# CanToUart.net
KiCad netlist of a schematic drawn in EasyEDA Pro
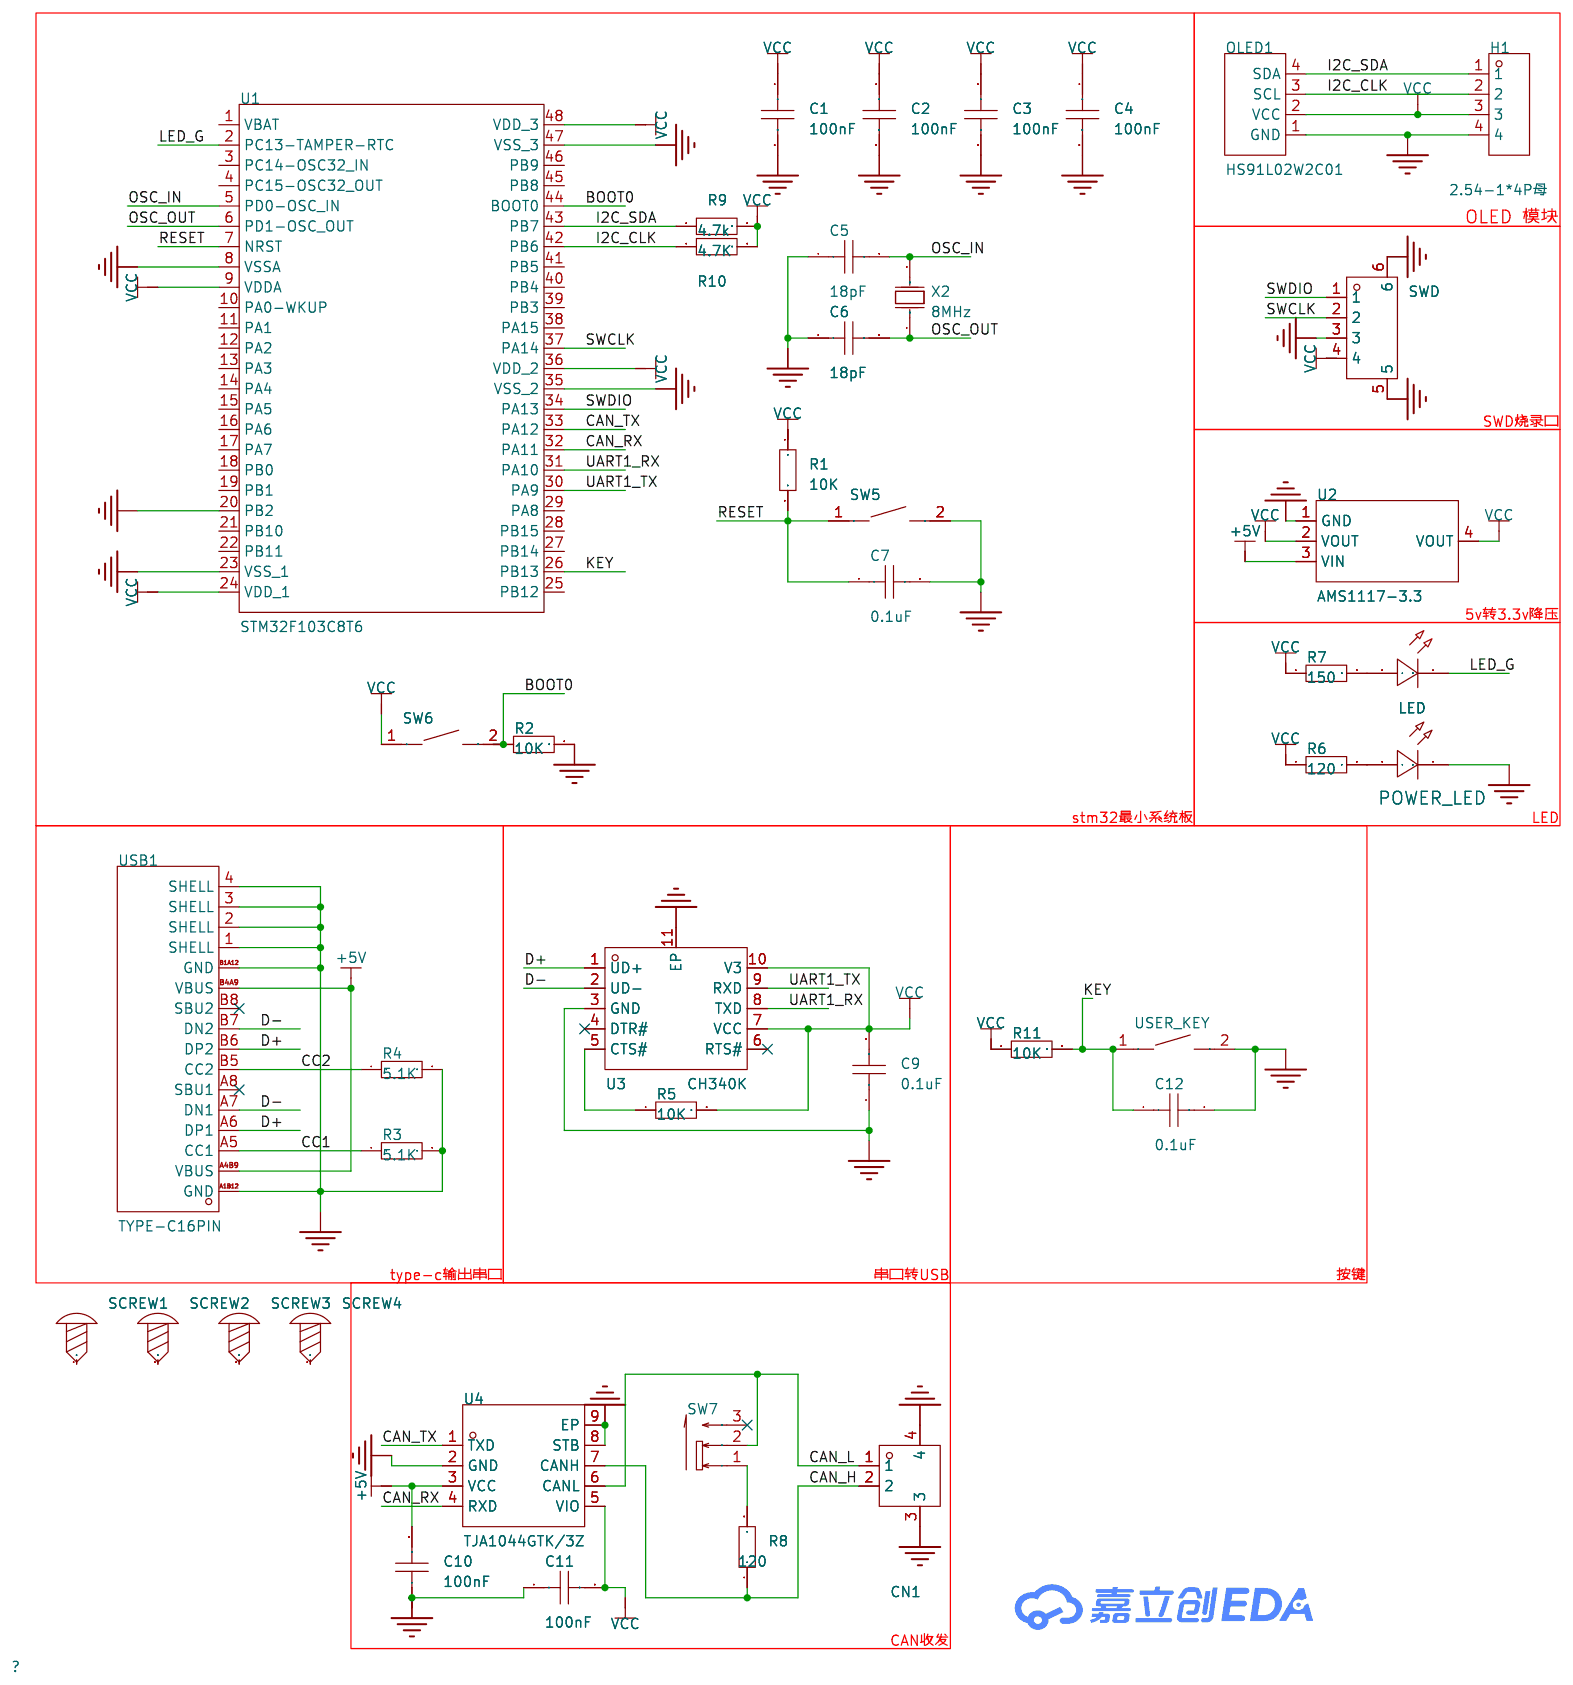
[diagram p0: schematic sheet]

(export (version "E")
  (design (tool "Eeschema 10.0.6"))
  (components
    (comp (ref "C1")
      (value "100nF")
      (footprint "easyedapro:C0603")
      (description "容值:100nF;精度:±10%;额定电压:50V;温度系数:X7R;")
      (fields
        (field (name "Manufacturer Part") "CGA0603X7R104K500JT")
        (field (name "Manufacturer") "HRE(芯声)")
      )
      (libsource (lib "easyedapro") (part "CGA0603X7R104K500JT"))
    )
    (comp (ref "C2")
      (value "100nF")
      (footprint "easyedapro:C0603")
      (description "容值:100nF;精度:±10%;额定电压:50V;温度系数:X7R;")
      (fields
        (field (name "Manufacturer Part") "CGA0603X7R104K500JT")
        (field (name "Manufacturer") "HRE(芯声)")
      )
      (libsource (lib "easyedapro") (part "CGA0603X7R104K500JT"))
    )
    (comp (ref "C3")
      (value "100nF")
      (footprint "easyedapro:C0603")
      (description "容值:100nF;精度:±10%;额定电压:50V;温度系数:X7R;")
      (fields
        (field (name "Manufacturer Part") "CGA0603X7R104K500JT")
        (field (name "Manufacturer") "HRE(芯声)")
      )
      (libsource (lib "easyedapro") (part "CGA0603X7R104K500JT"))
    )
    (comp (ref "C4")
      (value "100nF")
      (footprint "easyedapro:C0603")
      (description "容值:100nF;精度:±10%;额定电压:50V;温度系数:X7R;")
      (fields
        (field (name "Manufacturer Part") "CGA0603X7R104K500JT")
        (field (name "Manufacturer") "HRE(芯声)")
      )
      (libsource (lib "easyedapro") (part "CGA0603X7R104K500JT"))
    )
    (comp (ref "C5")
      (value "18pF")
      (footprint "easyedapro:C0603")
      (libsource (lib "easyedapro") (part "Capacitance"))
    )
    (comp (ref "C6")
      (value "18pF")
      (footprint "easyedapro:C0603")
      (libsource (lib "easyedapro") (part "Capacitance"))
    )
    (comp (ref "C7")
      (value "0.1uF")
      (footprint "easyedapro:C0603")
      (libsource (lib "easyedapro") (part "Capacitance"))
    )
    (comp (ref "C9")
      (value "0.1uF")
      (footprint "easyedapro:C0603")
      (libsource (lib "easyedapro") (part "Capacitance"))
    )
    (comp (ref "C10")
      (value "100nF")
      (footprint "easyedapro:C0603")
      (libsource (lib "easyedapro") (part "Capacitance"))
    )
    (comp (ref "C11")
      (value "100nF")
      (footprint "easyedapro:C0603")
      (libsource (lib "easyedapro") (part "Capacitance"))
    )
    (comp (ref "C12")
      (value "0.1uF")
      (footprint "easyedapro:C0603")
      (libsource (lib "easyedapro") (part "Capacitance"))
    )
    (comp (ref "CN1")
      (value "WAFER-GH1.25-2PWB")
      (footprint "easyedapro:CONN-TH_2P-P1.25_XUNPU_WAFER-GH1.25-2PWB")
      (fields (field (name "Manufacturer") "XUNPU(讯普)"))
      (libsource (lib "easyedapro") (part "WAFER-GH1.25-2PWB"))
    )
    (comp (ref "H1")
      (value "2.54-1*4P母")
      (footprint "easyedapro:HDR-TH_4P-P2.54-V-F")
      (fields (field (name "Manufacturer") "BOOMELE(博穆精密)"))
      (libsource (lib "easyedapro") (part "2.54-1*4P母"))
    )
    (comp (ref "LED")
      (value "~")
      (footprint "easyedapro:LED_0603")
      (libsource (lib "easyedapro") (part "LED_G"))
    )
    (comp (ref "OLED1")
      (value "HS91L02W2C01")
      (footprint "easyedapro:OLED-TH_L38.0-W12.0_HS91L02W2C01")
      (description "主控芯片:SSD1306;接口类型:I2C;尺寸(inch):0.91;像素分辨率:128x32;")
      (fields (field (name "Manufacturer") "HS(汉昇)"))
      (libsource (lib "easyedapro") (part "HS91L02W2C01"))
    )
    (comp (ref "POWER_LED")
      (value "~")
      (footprint "easyedapro:LED_0603")
      (libsource (lib "easyedapro") (part "LED_R"))
    )
    (comp (ref "R1") (value "10K") (footprint "easyedapro:R0603") (libsource (lib "easyedapro") (part "电阻")))
    (comp (ref "R2") (value "10K") (footprint "easyedapro:R0603") (libsource (lib "easyedapro") (part "电阻")))
    (comp (ref "R3") (value "5.1K") (footprint "easyedapro:R0603") (libsource (lib "easyedapro") (part "电阻")))
    (comp (ref "R4") (value "5.1K") (footprint "easyedapro:R0603") (libsource (lib "easyedapro") (part "电阻")))
    (comp (ref "R5") (value "10K") (footprint "easyedapro:R0603") (libsource (lib "easyedapro") (part "电阻")))
    (comp (ref "R6") (value "120") (footprint "easyedapro:R0603") (libsource (lib "easyedapro") (part "电阻")))
    (comp (ref "R7") (value "150") (footprint "easyedapro:R0603") (libsource (lib "easyedapro") (part "电阻")))
    (comp (ref "R8") (value "120") (footprint "easyedapro:R0603") (libsource (lib "easyedapro") (part "电阻")))
    (comp (ref "R9") (value "4.7k") (footprint "easyedapro:R0603") (libsource (lib "easyedapro") (part "电阻")))
    (comp (ref "R10")
      (value "4.7K")
      (footprint "easyedapro:R0603")
      (libsource (lib "easyedapro") (part "电阻"))
    )
    (comp (ref "R11") (value "10K") (footprint "easyedapro:R0603") (libsource (lib "easyedapro") (part "电阻")))
    (comp (ref "SCREW1")
      (value "~")
      (footprint "easyedapro:M2螺丝")
      (libsource (lib "easyedapro") (part "螺丝孔"))
    )
    (comp (ref "SCREW2")
      (value "~")
      (footprint "easyedapro:M2螺丝")
      (libsource (lib "easyedapro") (part "螺丝孔"))
    )
    (comp (ref "SCREW3")
      (value "~")
      (footprint "easyedapro:M2螺丝")
      (libsource (lib "easyedapro") (part "螺丝孔"))
    )
    (comp (ref "SCREW4")
      (value "~")
      (footprint "easyedapro:M2螺丝")
      (libsource (lib "easyedapro") (part "螺丝孔"))
    )
    (comp (ref "SW5")
      (value "TS-1088-AR02016")
      (footprint "easyedapro:SW-SMD_L3.9-W3.0-P4.45")
      (fields (field (name "Manufacturer") "XUNPU(讯普)"))
      (libsource (lib "easyedapro") (part "TS-1088-AR02016"))
    )
    (comp (ref "SW6")
      (value "TS-1088-AR02016")
      (footprint "easyedapro:SW-SMD_L3.9-W3.0-P4.45")
      (fields (field (name "Manufacturer") "XUNPU(讯普)"))
      (libsource (lib "easyedapro") (part "TS-1088-AR02016"))
    )
    (comp (ref "SW7")
      (value "MST-22D18G2 3J")
      (footprint "easyedapro:SW-SMD_SHOUHAN_MST-22D18G23J_C2875122")
      (description "电路结构:单刀双掷;安装方式:立贴;开关颜色:-;额定电流(DC):50mA;额定电压(DC):12V;额定电流(AC):-;额定电压(AC):-;机械寿命:1万次;")
      (fields (field (name "Manufacturer") "SHOU HAN(首韩)"))
      (libsource (lib "easyedapro") (part "MST-22D18G2 3J_C2875122"))
    )
    (comp (ref "SWD")
      (value "532610471")
      (footprint "easyedapro:CONN-SMD_4P-P1.25_53261-0471")
      (fields (field (name "Manufacturer") "MOLEX"))
      (libsource (lib "easyedapro") (part "53261-0471"))
    )
    (comp (ref "U1")
      (value "STM32F103C8T6")
      (footprint "easyedapro:LQFP-48_L7.0-W7.0-P0.50-LS9.0-BL")
      (description "CPU内核:ARM-M3;CPU最大主频:72MHz;应用领域:-;")
      (fields (field (name "Manufacturer") "ST(意法半导体)"))
      (libsource (lib "easyedapro") (part "STM32F103C8T6"))
    )
    (comp (ref "U2")
      (value "AMS1117-3.3")
      (footprint "easyedapro:SOT-223-3_L6.5-W3.4-P2.30-LS7.0-BR")
      (description "输出类型:固定;工作电压:16V;输出电压:3.3V;输出电流:1A;电源纹波抑制比(PSRR):72dB@(120Hz);输出极性:正极;")
      (fields (field (name "Manufacturer") "AMS"))
      (libsource (lib "easyedapro") (part "AMS1117-3.3"))
    )
    (comp (ref "U3")
      (value "CH340K")
      (footprint "easyedapro:ESOP-10_L4.9-W3.9-P1.00-LS6.2-BL-EP")
      (description "应用功能:USB转串口;接口协议:USB 2.0;通道数:-;数据速率:2Mbps;")
      (fields (field (name "Manufacturer") "WCH(南京沁恒)"))
      (libsource (lib "easyedapro") (part "CH340K"))
    )
    (comp (ref "U4")
      (value "TJA1044GTK/3Z")
      (footprint "easyedapro:HVSON-8_L3.0-W3.0-P0.65-BL-EP")
      (description "类型:CAN收发器;数据速率:5Mbps;")
      (fields (field (name "Manufacturer") "NXP(恩智浦)"))
      (libsource (lib "easyedapro") (part "TJA1044GTK/3Z"))
    )
    (comp (ref "USB1")
      (value "TYPE-C16PIN")
      (footprint "easyedapro:USB-C-SMD_TYPE-C16PIN")
      (description "连接器类型:Type-C;协议标准:USB 3.1;公母:母;安装方式:卧贴;触点数量:16P;端口数量:1;额定电流 - 电源:3A;工作温度:-40°C~+85°C;")
      (fields (field (name "Manufacturer") "SHOU HAN(首韩)"))
      (libsource (lib "easyedapro") (part "TYPE-C16PIN"))
    )
    (comp (ref "USER_KEY")
      (value "TS-1088-AR02016")
      (footprint "easyedapro:SW-SMD_L3.9-W3.0-P4.45")
      (fields (field (name "Manufacturer") "XUNPU(讯普)"))
      (libsource (lib "easyedapro") (part "TS-1088-AR02016"))
    )
    (comp (ref "X2")
      (value "8MHz")
      (footprint "easyedapro:CRYSTAL-SMD_L5.0-W3.2")
      (description "晶振类型:贴片晶振;频率:8MHz;常温频差:±10ppm;负载电容:20pF;频率稳定度:±20ppm;")
      (fields (field (name "Manufacturer Part") "X50328MSB2GI") (field (name "Manufacturer") "YXC(扬兴晶振)"))
      (libsource (lib "easyedapro") (part "X50328MSB2GI"))
    )
  )
  (nets
    (net (code "1") (name "+5V") (class "Default")
      (node (ref "C10") (pin "2") (pinfunction "2_2") (pintype "input"))
      (node (ref "U2") (pin "3") (pinfunction "VIN_3") (pintype "unspecified"))
      (node (ref "U4") (pin "3") (pinfunction "VCC_3") (pintype "unspecified"))
      (node (ref "USB1") (pin "A4B9") (pinfunction "VBUS_A4B9") (pintype "unspecified"))
      (node (ref "USB1") (pin "B4A9") (pinfunction "VBUS_B4A9") (pintype "unspecified"))
    )
    (net (code "2") (name "/BOOT0") (class "Default")
      (node (ref "R2") (pin "1") (pinfunction "1_1") (pintype "input"))
      (node (ref "SW6") (pin "2") (pinfunction "2_2") (pintype "unspecified"))
      (node (ref "U1") (pin "44") (pinfunction "BOOT0_44") (pintype "unspecified"))
    )
    (net (code "3") (name "/CAN_H") (class "Default")
      (node (ref "CN1") (pin "2") (pinfunction "2_2") (pintype "unspecified"))
      (node (ref "R8") (pin "1") (pinfunction "1_1") (pintype "input"))
      (node (ref "U4") (pin "7") (pinfunction "CANH_7") (pintype "unspecified"))
    )
    (net (code "4") (name "/CAN_L") (class "Default")
      (node (ref "CN1") (pin "1") (pinfunction "1_1") (pintype "unspecified"))
      (node (ref "SW7") (pin "2") (pinfunction "2_2") (pintype "unspecified"))
      (node (ref "U4") (pin "6") (pinfunction "CANL_6") (pintype "unspecified"))
    )
    (net (code "5") (name "/CAN_RX") (class "Default")
      (node (ref "U1") (pin "32") (pinfunction "PA11_32") (pintype "unspecified"))
      (node (ref "U4") (pin "4") (pinfunction "RXD_4") (pintype "unspecified"))
    )
    (net (code "6") (name "/CAN_TX") (class "Default")
      (node (ref "U1") (pin "33") (pinfunction "PA12_33") (pintype "unspecified"))
      (node (ref "U4") (pin "1") (pinfunction "TXD_1") (pintype "unspecified"))
    )
    (net (code "7") (name "/CC1") (class "Default")
      (node (ref "R3") (pin "1") (pinfunction "1_1") (pintype "input"))
      (node (ref "USB1") (pin "A5") (pinfunction "CC1_A5") (pintype "unspecified"))
    )
    (net (code "8") (name "/CC2") (class "Default")
      (node (ref "R4") (pin "1") (pinfunction "1_1") (pintype "input"))
      (node (ref "USB1") (pin "B5") (pinfunction "CC2_B5") (pintype "unspecified"))
    )
    (net (code "9") (name "/D+") (class "Default")
      (node (ref "U3") (pin "1") (pinfunction "UD+_1") (pintype "unspecified"))
      (node (ref "USB1") (pin "A6") (pinfunction "DP1_A6") (pintype "unspecified"))
      (node (ref "USB1") (pin "B6") (pinfunction "DP2_B6") (pintype "unspecified"))
    )
    (net (code "10") (name "/D-") (class "Default")
      (node (ref "U3") (pin "2") (pinfunction "UD-_2") (pintype "unspecified"))
      (node (ref "USB1") (pin "A7") (pinfunction "DN1_A7") (pintype "unspecified"))
      (node (ref "USB1") (pin "B7") (pinfunction "DN2_B7") (pintype "unspecified"))
    )
    (net (code "11") (name "/I2C_CLK") (class "Default")
      (node (ref "H1") (pin "2") (pinfunction "2_2") (pintype "unspecified"))
      (node (ref "OLED1") (pin "3") (pinfunction "SCL_3") (pintype "unspecified"))
      (node (ref "R10") (pin "1") (pinfunction "1_1") (pintype "input"))
      (node (ref "U1") (pin "42") (pinfunction "PB6_42") (pintype "unspecified"))
    )
    (net (code "12") (name "/I2C_SDA") (class "Default")
      (node (ref "H1") (pin "1") (pinfunction "1_1") (pintype "unspecified"))
      (node (ref "OLED1") (pin "4") (pinfunction "SDA_4") (pintype "unspecified"))
      (node (ref "R9") (pin "1") (pinfunction "1_1") (pintype "input"))
      (node (ref "U1") (pin "43") (pinfunction "PB7_43") (pintype "unspecified"))
    )
    (net (code "13") (name "/KEY") (class "Default")
      (node (ref "C12") (pin "1") (pinfunction "1_1") (pintype "input"))
      (node (ref "R11") (pin "2") (pinfunction "2_2") (pintype "input"))
      (node (ref "U1") (pin "26") (pinfunction "PB13_26") (pintype "unspecified"))
      (node (ref "USER_KEY") (pin "1") (pinfunction "1_1") (pintype "unspecified"))
    )
    (net (code "14") (name "/LED_G") (class "Default")
      (node (ref "LED") (pin "1") (pinfunction "C_1") (pintype "input"))
      (node (ref "U1") (pin "2") (pinfunction "PC13-TAMPER-RTC_2") (pintype "unspecified"))
    )
    (net (code "15") (name "/OSC_IN") (class "Default")
      (node (ref "C5") (pin "2") (pinfunction "2_2") (pintype "input"))
      (node (ref "U1") (pin "5") (pinfunction "PD0-OSC_IN_5") (pintype "unspecified"))
      (node (ref "X2") (pin "2") (pinfunction "OSC2_2") (pintype "input"))
    )
    (net (code "16") (name "/OSC_OUT") (class "Default")
      (node (ref "C6") (pin "2") (pinfunction "2_2") (pintype "input"))
      (node (ref "U1") (pin "6") (pinfunction "PD1-OSC_OUT_6") (pintype "unspecified"))
      (node (ref "X2") (pin "1") (pinfunction "OSC1_1") (pintype "input"))
    )
    (net (code "17") (name "/RESET") (class "Default")
      (node (ref "C7") (pin "1") (pinfunction "1_1") (pintype "input"))
      (node (ref "R1") (pin "2") (pinfunction "2_2") (pintype "input"))
      (node (ref "SW5") (pin "1") (pinfunction "1_1") (pintype "unspecified"))
      (node (ref "U1") (pin "7") (pinfunction "NRST_7") (pintype "unspecified"))
    )
    (net (code "18") (name "/SWCLK") (class "Default")
      (node (ref "SWD") (pin "2") (pinfunction "2_2") (pintype "unspecified"))
      (node (ref "U1") (pin "37") (pinfunction "PA14_37") (pintype "unspecified"))
    )
    (net (code "19") (name "/SWDIO") (class "Default")
      (node (ref "SWD") (pin "1") (pinfunction "1_1") (pintype "unspecified"))
      (node (ref "U1") (pin "34") (pinfunction "PA13_34") (pintype "unspecified"))
    )
    (net (code "20") (name "/UART1_RX") (class "Default")
      (node (ref "U1") (pin "31") (pinfunction "PA10_31") (pintype "unspecified"))
      (node (ref "U3") (pin "8") (pinfunction "TXD_8") (pintype "unspecified"))
    )
    (net (code "21") (name "/UART1_TX") (class "Default")
      (node (ref "U1") (pin "30") (pinfunction "PA9_30") (pintype "unspecified"))
      (node (ref "U3") (pin "9") (pinfunction "RXD_9") (pintype "unspecified"))
    )
    (net (code "22") (name "GND") (class "Default")
      (node (ref "C1") (pin "2") (pinfunction "2_2") (pintype "unspecified"))
      (node (ref "C10") (pin "1") (pinfunction "1_1") (pintype "input"))
      (node (ref "C11") (pin "1") (pinfunction "1_1") (pintype "input"))
      (node (ref "C12") (pin "2") (pinfunction "2_2") (pintype "input"))
      (node (ref "C2") (pin "2") (pinfunction "2_2") (pintype "unspecified"))
      (node (ref "C3") (pin "2") (pinfunction "2_2") (pintype "unspecified"))
      (node (ref "C4") (pin "2") (pinfunction "2_2") (pintype "unspecified"))
      (node (ref "C5") (pin "1") (pinfunction "1_1") (pintype "input"))
      (node (ref "C6") (pin "1") (pinfunction "1_1") (pintype "input"))
      (node (ref "C7") (pin "2") (pinfunction "2_2") (pintype "input"))
      (node (ref "C9") (pin "1") (pinfunction "1_1") (pintype "input"))
      (node (ref "CN1") (pin "3") (pinfunction "3_3") (pintype "unspecified"))
      (node (ref "CN1") (pin "4") (pinfunction "4_4") (pintype "unspecified"))
      (node (ref "H1") (pin "4") (pinfunction "4_4") (pintype "unspecified"))
      (node (ref "OLED1") (pin "1") (pinfunction "GND_1") (pintype "unspecified"))
      (node (ref "POWER_LED") (pin "1") (pinfunction "C_1") (pintype "input"))
      (node (ref "R2") (pin "2") (pinfunction "2_2") (pintype "input"))
      (node (ref "R3") (pin "2") (pinfunction "2_2") (pintype "input"))
      (node (ref "R4") (pin "2") (pinfunction "2_2") (pintype "input"))
      (node (ref "SW5") (pin "2") (pinfunction "2_2") (pintype "unspecified"))
      (node (ref "SWD") (pin "3") (pinfunction "3_3") (pintype "unspecified"))
      (node (ref "SWD") (pin "5") (pinfunction "5_5") (pintype "unspecified"))
      (node (ref "SWD") (pin "6") (pinfunction "6_6") (pintype "unspecified"))
      (node (ref "U1") (pin "20") (pinfunction "PB2_20") (pintype "unspecified"))
      (node (ref "U1") (pin "23") (pinfunction "VSS_1_23") (pintype "unspecified"))
      (node (ref "U1") (pin "35") (pinfunction "VSS_2_35") (pintype "unspecified"))
      (node (ref "U1") (pin "47") (pinfunction "VSS_3_47") (pintype "unspecified"))
      (node (ref "U1") (pin "8") (pinfunction "VSSA_8") (pintype "unspecified"))
      (node (ref "U2") (pin "1") (pinfunction "GND_1") (pintype "unspecified"))
      (node (ref "U3") (pin "11") (pinfunction "EP_11") (pintype "unspecified"))
      (node (ref "U3") (pin "3") (pinfunction "GND_3") (pintype "unspecified"))
      (node (ref "U4") (pin "2") (pinfunction "GND_2") (pintype "unspecified"))
      (node (ref "U4") (pin "8") (pinfunction "STB_8") (pintype "unspecified"))
      (node (ref "U4") (pin "9") (pinfunction "EP_9") (pintype "unspecified"))
      (node (ref "USB1") (pin "1") (pinfunction "SHELL_1") (pintype "unspecified"))
      (node (ref "USB1") (pin "2") (pinfunction "SHELL_2") (pintype "unspecified"))
      (node (ref "USB1") (pin "3") (pinfunction "SHELL_3") (pintype "unspecified"))
      (node (ref "USB1") (pin "4") (pinfunction "SHELL_4") (pintype "unspecified"))
      (node (ref "USB1") (pin "A1B12") (pinfunction "GND_A1B12") (pintype "unspecified"))
      (node (ref "USB1") (pin "B1A12") (pinfunction "GND_B1A12") (pintype "unspecified"))
      (node (ref "USER_KEY") (pin "2") (pinfunction "2_2") (pintype "unspecified"))
    )
    (net (code "23") (name "Net-(LED-A)") (class "Default")
      (node (ref "LED") (pin "2") (pinfunction "A_2") (pintype "input"))
      (node (ref "R7") (pin "2") (pinfunction "2_2") (pintype "input"))
    )
    (net (code "24") (name "Net-(POWER_LED-A)") (class "Default")
      (node (ref "POWER_LED") (pin "2") (pinfunction "A_2") (pintype "input"))
      (node (ref "R6") (pin "2") (pinfunction "2_2") (pintype "input"))
    )
    (net (code "25") (name "Net-(R8-Pad2)") (class "Default")
      (node (ref "R8") (pin "2") (pinfunction "2_2") (pintype "input"))
      (node (ref "SW7") (pin "1") (pinfunction "1_1") (pintype "unspecified"))
    )
    (net (code "26") (name "Net-(U3-CTS#)") (class "Default")
      (node (ref "R5") (pin "1") (pinfunction "1_1") (pintype "input"))
      (node (ref "U3") (pin "5") (pinfunction "CTS#_5") (pintype "unspecified"))
    )
    (net (code "27") (name "VCC") (class "Default")
      (node (ref "C1") (pin "1") (pinfunction "1_1") (pintype "unspecified"))
      (node (ref "C11") (pin "2") (pinfunction "2_2") (pintype "input"))
      (node (ref "C2") (pin "1") (pinfunction "1_1") (pintype "unspecified"))
      (node (ref "C3") (pin "1") (pinfunction "1_1") (pintype "unspecified"))
      (node (ref "C4") (pin "1") (pinfunction "1_1") (pintype "unspecified"))
      (node (ref "C9") (pin "2") (pinfunction "2_2") (pintype "input"))
      (node (ref "H1") (pin "3") (pinfunction "3_3") (pintype "unspecified"))
      (node (ref "OLED1") (pin "2") (pinfunction "VCC_2") (pintype "unspecified"))
      (node (ref "R1") (pin "1") (pinfunction "1_1") (pintype "input"))
      (node (ref "R10") (pin "2") (pinfunction "2_2") (pintype "input"))
      (node (ref "R11") (pin "1") (pinfunction "1_1") (pintype "input"))
      (node (ref "R5") (pin "2") (pinfunction "2_2") (pintype "input"))
      (node (ref "R6") (pin "1") (pinfunction "1_1") (pintype "input"))
      (node (ref "R7") (pin "1") (pinfunction "1_1") (pintype "input"))
      (node (ref "R9") (pin "2") (pinfunction "2_2") (pintype "input"))
      (node (ref "SW6") (pin "1") (pinfunction "1_1") (pintype "unspecified"))
      (node (ref "SWD") (pin "4") (pinfunction "4_4") (pintype "unspecified"))
      (node (ref "U1") (pin "24") (pinfunction "VDD_1_24") (pintype "unspecified"))
      (node (ref "U1") (pin "36") (pinfunction "VDD_2_36") (pintype "unspecified"))
      (node (ref "U1") (pin "48") (pinfunction "VDD_3_48") (pintype "unspecified"))
      (node (ref "U1") (pin "9") (pinfunction "VDDA_9") (pintype "unspecified"))
      (node (ref "U2") (pin "2") (pinfunction "VOUT_2") (pintype "unspecified"))
      (node (ref "U2") (pin "4") (pinfunction "VOUT_4") (pintype "unspecified"))
      (node (ref "U3") (pin "10") (pinfunction "V3_10") (pintype "unspecified"))
      (node (ref "U3") (pin "7") (pinfunction "VCC_7") (pintype "unspecified"))
      (node (ref "U4") (pin "5") (pinfunction "VIO_5") (pintype "unspecified"))
    )
    (net (code "28") (name "unconnected-(SCREW1-Pad1)") (class "Default")
      (node (ref "SCREW1") (pin "1") (pinfunction "1_1") (pintype "input"))
    )
    (net (code "29") (name "unconnected-(SCREW2-Pad1)") (class "Default")
      (node (ref "SCREW2") (pin "1") (pinfunction "1_1") (pintype "input"))
    )
    (net (code "30") (name "unconnected-(SCREW3-Pad1)") (class "Default")
      (node (ref "SCREW3") (pin "1") (pinfunction "1_1") (pintype "input"))
    )
    (net (code "31") (name "unconnected-(SCREW4-Pad1)") (class "Default")
      (node (ref "SCREW4") (pin "1") (pinfunction "1_1") (pintype "input"))
    )
    (net (code "32") (name "unconnected-(SW7-Pad3)") (class "Default")
      (node (ref "SW7") (pin "3") (pinfunction "3_3") (pintype "unspecified+no_connect"))
    )
    (net (code "33") (name "unconnected-(U1-PA0-WKUP-Pad10)") (class "Default")
      (node (ref "U1") (pin "10") (pinfunction "PA0-WKUP_10") (pintype "unspecified"))
    )
    (net (code "34") (name "unconnected-(U1-PA1-Pad11)") (class "Default")
      (node (ref "U1") (pin "11") (pinfunction "PA1_11") (pintype "unspecified"))
    )
    (net (code "35") (name "unconnected-(U1-PA2-Pad12)") (class "Default")
      (node (ref "U1") (pin "12") (pinfunction "PA2_12") (pintype "unspecified"))
    )
    (net (code "36") (name "unconnected-(U1-PA3-Pad13)") (class "Default")
      (node (ref "U1") (pin "13") (pinfunction "PA3_13") (pintype "unspecified"))
    )
    (net (code "37") (name "unconnected-(U1-PA4-Pad14)") (class "Default")
      (node (ref "U1") (pin "14") (pinfunction "PA4_14") (pintype "unspecified"))
    )
    (net (code "38") (name "unconnected-(U1-PA5-Pad15)") (class "Default")
      (node (ref "U1") (pin "15") (pinfunction "PA5_15") (pintype "unspecified"))
    )
    (net (code "39") (name "unconnected-(U1-PA6-Pad16)") (class "Default")
      (node (ref "U1") (pin "16") (pinfunction "PA6_16") (pintype "unspecified"))
    )
    (net (code "40") (name "unconnected-(U1-PA7-Pad17)") (class "Default")
      (node (ref "U1") (pin "17") (pinfunction "PA7_17") (pintype "unspecified"))
    )
    (net (code "41") (name "unconnected-(U1-PA8-Pad29)") (class "Default")
      (node (ref "U1") (pin "29") (pinfunction "PA8_29") (pintype "unspecified"))
    )
    (net (code "42") (name "unconnected-(U1-PA15-Pad38)") (class "Default")
      (node (ref "U1") (pin "38") (pinfunction "PA15_38") (pintype "unspecified"))
    )
    (net (code "43") (name "unconnected-(U1-PB0-Pad18)") (class "Default")
      (node (ref "U1") (pin "18") (pinfunction "PB0_18") (pintype "unspecified"))
    )
    (net (code "44") (name "unconnected-(U1-PB1-Pad19)") (class "Default")
      (node (ref "U1") (pin "19") (pinfunction "PB1_19") (pintype "unspecified"))
    )
    (net (code "45") (name "unconnected-(U1-PB3-Pad39)") (class "Default")
      (node (ref "U1") (pin "39") (pinfunction "PB3_39") (pintype "unspecified"))
    )
    (net (code "46") (name "unconnected-(U1-PB4-Pad40)") (class "Default")
      (node (ref "U1") (pin "40") (pinfunction "PB4_40") (pintype "unspecified"))
    )
    (net (code "47") (name "unconnected-(U1-PB5-Pad41)") (class "Default")
      (node (ref "U1") (pin "41") (pinfunction "PB5_41") (pintype "unspecified"))
    )
    (net (code "48") (name "unconnected-(U1-PB8-Pad45)") (class "Default")
      (node (ref "U1") (pin "45") (pinfunction "PB8_45") (pintype "unspecified"))
    )
    (net (code "49") (name "unconnected-(U1-PB9-Pad46)") (class "Default")
      (node (ref "U1") (pin "46") (pinfunction "PB9_46") (pintype "unspecified"))
    )
    (net (code "50") (name "unconnected-(U1-PB10-Pad21)") (class "Default")
      (node (ref "U1") (pin "21") (pinfunction "PB10_21") (pintype "unspecified"))
    )
    (net (code "51") (name "unconnected-(U1-PB11-Pad22)") (class "Default")
      (node (ref "U1") (pin "22") (pinfunction "PB11_22") (pintype "unspecified"))
    )
    (net (code "52") (name "unconnected-(U1-PB12-Pad25)") (class "Default")
      (node (ref "U1") (pin "25") (pinfunction "PB12_25") (pintype "unspecified"))
    )
    (net (code "53") (name "unconnected-(U1-PB14-Pad27)") (class "Default")
      (node (ref "U1") (pin "27") (pinfunction "PB14_27") (pintype "unspecified"))
    )
    (net (code "54") (name "unconnected-(U1-PB15-Pad28)") (class "Default")
      (node (ref "U1") (pin "28") (pinfunction "PB15_28") (pintype "unspecified"))
    )
    (net (code "55") (name "unconnected-(U1-PC14-OSC32_IN-Pad3)") (class "Default")
      (node (ref "U1") (pin "3") (pinfunction "PC14-OSC32_IN_3") (pintype "unspecified"))
    )
    (net (code "56") (name "unconnected-(U1-PC15-OSC32_OUT-Pad4)") (class "Default")
      (node (ref "U1") (pin "4") (pinfunction "PC15-OSC32_OUT_4") (pintype "unspecified"))
    )
    (net (code "57") (name "unconnected-(U1-VBAT-Pad1)") (class "Default")
      (node (ref "U1") (pin "1") (pinfunction "VBAT_1") (pintype "unspecified"))
    )
    (net (code "58") (name "unconnected-(U3-DTR#-Pad4)") (class "Default")
      (node (ref "U3") (pin "4") (pinfunction "DTR#_4") (pintype "unspecified+no_connect"))
    )
    (net (code "59") (name "unconnected-(U3-RTS#-Pad6)") (class "Default")
      (node (ref "U3") (pin "6") (pinfunction "RTS#_6") (pintype "unspecified+no_connect"))
    )
    (net (code "60") (name "unconnected-(USB1-SBU1-PadA8)") (class "Default")
      (node (ref "USB1") (pin "A8") (pinfunction "SBU1_A8") (pintype "unspecified+no_connect"))
    )
    (net (code "61") (name "unconnected-(USB1-SBU2-PadB8)") (class "Default")
      (node (ref "USB1") (pin "B8") (pinfunction "SBU2_B8") (pintype "unspecified+no_connect"))
    )
  )
)
